# Motor_Driver.net
KiCad netlist of a schematic drawn in Altium Designer
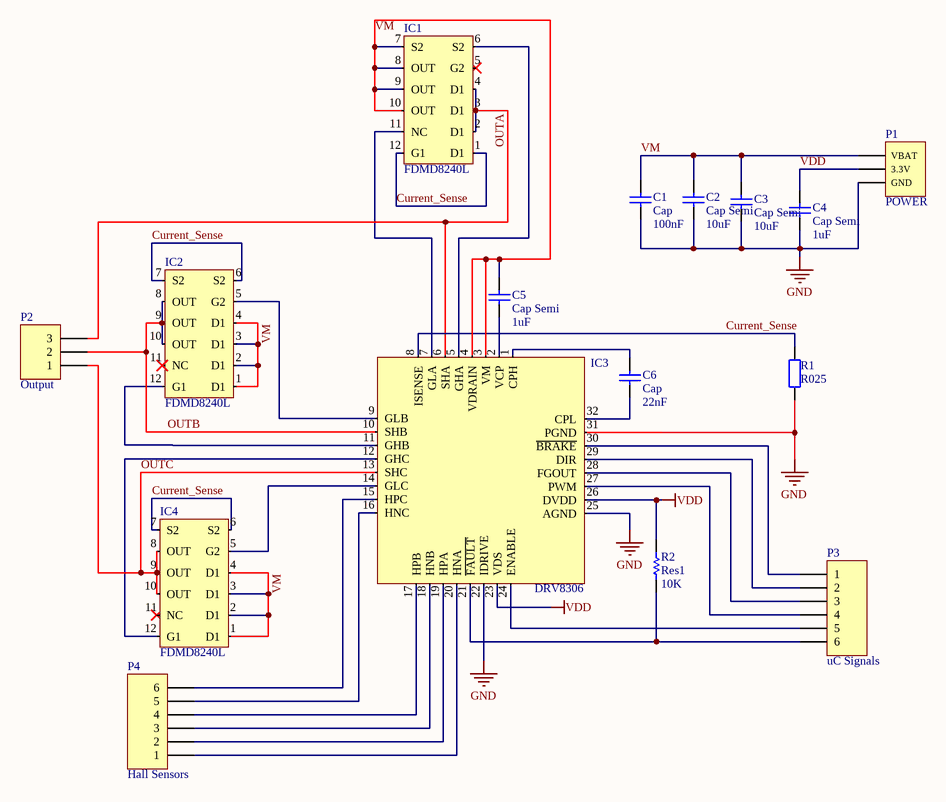
[diagram p0: Motor_Driver.SchDoc]

(export (version "E")
  (design (tool "Eeschema 10.0.6"))
  (components
    (comp (ref "C1")
      (value "Cap")
      (footprint "0402")
      (description "Multilayer Ceramic Capacitors MLCC - SMD/SMT 16volts 0.1uF 20% X7R")
      (fields (field (name "ALTIUM_VALUE") "100nF"))
      (libsource (lib "Miscellaneous Devices") (part "Cap"))
    )
    (comp (ref "C2")
      (value "Cap Semi")
      (footprint "CAP_TANT1206")
      (description "Tantalum Capacitors - Solid SMD 16V 10uF 1206 10% ESR=3Ohms")
      (fields (field (name "ALTIUM_VALUE") "10uF"))
      (libsource (lib "Miscellaneous Devices") (part "Cap Semi"))
    )
    (comp (ref "C3")
      (value "Cap Semi")
      (footprint "CAP_TANT1206")
      (description "Tantalum Capacitors - Solid SMD 16V 10uF 1206 10% ESR=3Ohms")
      (fields (field (name "ALTIUM_VALUE") "10uF"))
      (libsource (lib "Miscellaneous Devices") (part "Cap Semi"))
    )
    (comp (ref "C4")
      (value "Cap Semi")
      (footprint "0402")
      (description "Multilayer Ceramic Capacitors MLCC - SMD/SMT CGB 0402 16V 1uF JB 20%")
      (fields (field (name "ALTIUM_VALUE") "1uF"))
      (libsource (lib "Miscellaneous Devices") (part "Cap Semi"))
    )
    (comp (ref "C5")
      (value "Cap Semi")
      (footprint "0402")
      (description "Multilayer Ceramic Capacitors MLCC - SMD/SMT CGB 0402 16V 1uF JB 20%")
      (fields (field (name "ALTIUM_VALUE") "1uF"))
      (libsource (lib "Miscellaneous Devices") (part "Cap Semi"))
    )
    (comp (ref "C6")
      (value "Cap")
      (footprint "0402")
      (description "Capacitor")
      (fields (field (name "ALTIUM_VALUE") "22nF") (field (name "PUBLISHER") "Altium Limited"))
      (libsource (lib "Miscellaneous Devices") (part "Cap"))
    )
    (comp (ref "IC1")
      (value "FDMD8240L")
      (footprint "PQFN-12")
      (description "Dual N-Channel Power Trench MOSFET 40, 98A, 2.6mOhms")
      (libsource (lib "Motor_Driver") (part "FDMD8240L"))
    )
    (comp (ref "IC2")
      (value "FDMD8240L")
      (footprint "PQFN-12")
      (description "Dual N-Channel Power Trench MOSFET 40, 98A, 2.6mOhms")
      (libsource (lib "Motor_Driver") (part "FDMD8240L"))
    )
    (comp (ref "IC3")
      (value "DRV8306")
      (description "DRV8306 38-V Brushless DC Motor Controller")
      (libsource (lib "Motor_Driver") (part "DRV8306"))
    )
    (comp (ref "IC4")
      (value "FDMD8240L")
      (footprint "PQFN-12")
      (description "Dual N-Channel Power Trench MOSFET 40, 98A, 2.6mOhms")
      (libsource (lib "Motor_Driver") (part "FDMD8240L"))
    )
    (comp (ref "P1")
      (value "POWER")
      (footprint "HDR1X3")
      (description "Power Connector")
      (fields (field (name "PUBLISHER") "Altium Limited"))
      (libsource (lib "") (part "Header 3_1"))
    )
    (comp (ref "P2")
      (value "Output")
      (footprint "HDR1X3")
      (description "Motor Output")
      (fields (field (name "PUBLISHER") "Altium Limited"))
      (libsource (lib "Miscellaneous Connectors") (part "Header 3"))
    )
    (comp (ref "P3")
      (value "uC Signals")
      (footprint "HDR1X6")
      (description "Microcontroller connector")
      (fields (field (name "PUBLISHER") "Altium Limited"))
      (libsource (lib "Miscellaneous Connectors") (part "Header 6"))
    )
    (comp (ref "P4")
      (value "Hall Sensors")
      (footprint "HDR1X6")
      (description "Hall Sensors Connector")
      (fields (field (name "PUBLISHER") "Altium Limited"))
      (libsource (lib "") (part "Header 6_1"))
    )
    (comp (ref "R1")
      (value "R025")
      (footprint "RES2818")
      (description "Current Sense Resistors - SMD2818 10W .025ohms 1%")
      (libsource (lib "Motor_Driver") (part "WSHP2818"))
    )
    (comp (ref "R2")
      (value "Res1")
      (footprint "RES0402")
      (description "Thick Film Resistors - SMD 0.2watt 10Kohms 1% 100ppm")
      (fields (field (name "ALTIUM_VALUE") "10K"))
      (libsource (lib "Miscellaneous Devices") (part "Res1"))
    )
  )
  (nets
    (net (code "1") (name "/Current_Sense") (class "Default")
      (node (ref "IC1") (pin "1") (pinfunction "D1_1") (pintype "passive"))
      (node (ref "IC1") (pin "12") (pinfunction "G1_12") (pintype "passive"))
      (node (ref "IC2") (pin "6") (pinfunction "S2_6") (pintype "passive"))
      (node (ref "IC2") (pin "7") (pinfunction "S2_7") (pintype "passive"))
      (node (ref "IC3") (pin "8") (pinfunction "ISENSE_8") (pintype "input"))
      (node (ref "IC4") (pin "6") (pinfunction "S2_6") (pintype "passive"))
      (node (ref "IC4") (pin "7") (pinfunction "S2_7") (pintype "passive"))
      (node (ref "R1") (pin "2") (pinfunction "2_2") (pintype "passive"))
    )
    (net (code "2") (name "/OUTA") (class "Default")
      (node (ref "IC1") (pin "2") (pinfunction "D1_2") (pintype "passive"))
      (node (ref "IC1") (pin "3") (pinfunction "D1_3") (pintype "passive"))
      (node (ref "IC1") (pin "4") (pinfunction "D1_4") (pintype "passive"))
      (node (ref "IC3") (pin "6") (pinfunction "SHA_6") (pintype "input"))
      (node (ref "P2") (pin "3") (pinfunction "3_3") (pintype "passive"))
    )
    (net (code "3") (name "/OUTB") (class "Default")
      (node (ref "IC2") (pin "10") (pinfunction "OUT_10") (pintype "passive"))
      (node (ref "IC2") (pin "8") (pinfunction "OUT_8") (pintype "passive"))
      (node (ref "IC2") (pin "9") (pinfunction "OUT_9") (pintype "passive"))
      (node (ref "IC3") (pin "10") (pinfunction "SHB_10") (pintype "input"))
      (node (ref "P2") (pin "2") (pinfunction "2_2") (pintype "passive"))
    )
    (net (code "4") (name "/OUTC") (class "Default")
      (node (ref "IC3") (pin "13") (pinfunction "SHC_13") (pintype "input"))
      (node (ref "IC4") (pin "10") (pinfunction "OUT_10") (pintype "passive"))
      (node (ref "IC4") (pin "8") (pinfunction "OUT_8") (pintype "passive"))
      (node (ref "IC4") (pin "9") (pinfunction "OUT_9") (pintype "passive"))
      (node (ref "P2") (pin "1") (pinfunction "1_1") (pintype "passive"))
    )
    (net (code "5") (name "/VM") (class "Default")
      (node (ref "C1") (pin "2") (pinfunction "2_2") (pintype "passive"))
      (node (ref "C2") (pin "2") (pinfunction "2_2") (pintype "passive"))
      (node (ref "C3") (pin "2") (pinfunction "2_2") (pintype "passive"))
      (node (ref "C5") (pin "2") (pinfunction "2_2") (pintype "passive"))
      (node (ref "IC1") (pin "10") (pinfunction "OUT_10") (pintype "passive"))
      (node (ref "IC1") (pin "7") (pinfunction "S2_7") (pintype "passive"))
      (node (ref "IC1") (pin "8") (pinfunction "OUT_8") (pintype "passive"))
      (node (ref "IC1") (pin "9") (pinfunction "OUT_9") (pintype "passive"))
      (node (ref "IC2") (pin "1") (pinfunction "D1_1") (pintype "passive"))
      (node (ref "IC2") (pin "2") (pinfunction "D1_2") (pintype "passive"))
      (node (ref "IC2") (pin "3") (pinfunction "D1_3") (pintype "passive"))
      (node (ref "IC2") (pin "4") (pinfunction "D1_4") (pintype "passive"))
      (node (ref "IC3") (pin "3") (pinfunction "VM_3") (pintype "power_in"))
      (node (ref "IC3") (pin "4") (pinfunction "VDRAIN_4") (pintype "input"))
      (node (ref "IC4") (pin "1") (pinfunction "D1_1") (pintype "passive"))
      (node (ref "IC4") (pin "2") (pinfunction "D1_2") (pintype "passive"))
      (node (ref "IC4") (pin "3") (pinfunction "D1_3") (pintype "passive"))
      (node (ref "IC4") (pin "4") (pinfunction "D1_4") (pintype "passive"))
      (node (ref "P1") (pin "1") (pinfunction "VBAT_1") (pintype "passive"))
    )
    (net (code "6") (name "GND") (class "Default")
      (node (ref "C1") (pin "1") (pinfunction "1_1") (pintype "passive"))
      (node (ref "C2") (pin "1") (pinfunction "1_1") (pintype "passive"))
      (node (ref "C3") (pin "1") (pinfunction "1_1") (pintype "passive"))
      (node (ref "C4") (pin "1") (pinfunction "1_1") (pintype "passive"))
      (node (ref "IC3") (pin "22") (pinfunction "IDRIVE_22") (pintype "input"))
      (node (ref "IC3") (pin "25") (pinfunction "AGND_25") (pintype "power_in"))
      (node (ref "IC3") (pin "31") (pinfunction "PGND_31") (pintype "power_in"))
      (node (ref "P1") (pin "3") (pinfunction "GND_3") (pintype "passive"))
      (node (ref "R1") (pin "1") (pinfunction "1_1") (pintype "passive"))
    )
    (net (code "7") (name "Net-(IC1-NC)") (class "Default")
      (node (ref "IC1") (pin "11") (pinfunction "NC_11") (pintype "passive"))
      (node (ref "IC3") (pin "7") (pinfunction "GLA_7") (pintype "output"))
    )
    (net (code "8") (name "Net-(IC2-G1)") (class "Default")
      (node (ref "IC2") (pin "12") (pinfunction "G1_12") (pintype "passive"))
      (node (ref "IC3") (pin "11") (pinfunction "GHB_11") (pintype "output"))
    )
    (net (code "9") (name "Net-(IC2-G2)") (class "Default")
      (node (ref "IC2") (pin "5") (pinfunction "G2_5") (pintype "passive"))
      (node (ref "IC3") (pin "9") (pinfunction "GLB_9") (pintype "output"))
    )
    (net (code "10") (name "Net-(IC3-CPH)") (class "Default")
      (node (ref "C6") (pin "2") (pinfunction "2_2") (pintype "passive"))
      (node (ref "IC3") (pin "1") (pinfunction "CPH_1") (pintype "power_in"))
    )
    (net (code "11") (name "Net-(IC3-CPL)") (class "Default")
      (node (ref "C6") (pin "1") (pinfunction "1_1") (pintype "passive"))
      (node (ref "IC3") (pin "32") (pinfunction "CPL_32") (pintype "power_in"))
    )
    (net (code "12") (name "Net-(IC3-DIR)") (class "Default")
      (node (ref "IC3") (pin "29") (pinfunction "DIR_29") (pintype "input"))
      (node (ref "P3") (pin "2") (pinfunction "2_2") (pintype "passive"))
    )
    (net (code "13") (name "Net-(IC3-ENABLE)") (class "Default")
      (node (ref "IC3") (pin "24") (pinfunction "ENABLE_24") (pintype "input"))
      (node (ref "P3") (pin "5") (pinfunction "5_5") (pintype "passive"))
    )
    (net (code "14") (name "Net-(IC3-FGOUT)") (class "Default")
      (node (ref "IC3") (pin "28") (pinfunction "FGOUT_28") (pintype "open_collector"))
      (node (ref "P3") (pin "3") (pinfunction "3_3") (pintype "passive"))
    )
    (net (code "15") (name "Net-(IC3-GHA)") (class "Default")
      (node (ref "IC1") (pin "6") (pinfunction "S2_6") (pintype "passive"))
      (node (ref "IC3") (pin "5") (pinfunction "GHA_5") (pintype "output"))
    )
    (net (code "16") (name "Net-(IC3-GHC)") (class "Default")
      (node (ref "IC3") (pin "12") (pinfunction "GHC_12") (pintype "output"))
      (node (ref "IC4") (pin "12") (pinfunction "G1_12") (pintype "passive"))
    )
    (net (code "17") (name "Net-(IC3-GLC)") (class "Default")
      (node (ref "IC3") (pin "14") (pinfunction "GLC_14") (pintype "output"))
      (node (ref "IC4") (pin "5") (pinfunction "G2_5") (pintype "passive"))
    )
    (net (code "18") (name "Net-(IC3-HNA)") (class "Default")
      (node (ref "IC3") (pin "20") (pinfunction "HNA_20") (pintype "input"))
      (node (ref "P4") (pin "1") (pinfunction "1_1") (pintype "passive"))
    )
    (net (code "19") (name "Net-(IC3-HNB)") (class "Default")
      (node (ref "IC3") (pin "18") (pinfunction "HNB_18") (pintype "input"))
      (node (ref "P4") (pin "3") (pinfunction "3_3") (pintype "passive"))
    )
    (net (code "20") (name "Net-(IC3-HNC)") (class "Default")
      (node (ref "IC3") (pin "16") (pinfunction "HNC_16") (pintype "input"))
      (node (ref "P4") (pin "5") (pinfunction "5_5") (pintype "passive"))
    )
    (net (code "21") (name "Net-(IC3-HPA)") (class "Default")
      (node (ref "IC3") (pin "19") (pinfunction "HPA_19") (pintype "input"))
      (node (ref "P4") (pin "2") (pinfunction "2_2") (pintype "passive"))
    )
    (net (code "22") (name "Net-(IC3-HPB)") (class "Default")
      (node (ref "IC3") (pin "17") (pinfunction "HPB_17") (pintype "input"))
      (node (ref "P4") (pin "4") (pinfunction "4_4") (pintype "passive"))
    )
    (net (code "23") (name "Net-(IC3-HPC)") (class "Default")
      (node (ref "IC3") (pin "15") (pinfunction "HPC_15") (pintype "input"))
      (node (ref "P4") (pin "6") (pinfunction "6_6") (pintype "passive"))
    )
    (net (code "24") (name "Net-(IC3-PWM)") (class "Default")
      (node (ref "IC3") (pin "27") (pinfunction "PWM_27") (pintype "input"))
      (node (ref "P3") (pin "4") (pinfunction "4_4") (pintype "passive"))
    )
    (net (code "25") (name "Net-(IC3-VCP)") (class "Default")
      (node (ref "C5") (pin "1") (pinfunction "1_1") (pintype "passive"))
      (node (ref "IC3") (pin "2") (pinfunction "VCP_2") (pintype "power_in"))
    )
    (net (code "26") (name "Net-(IC3-~{BRAKE})") (class "Default")
      (node (ref "IC3") (pin "30") (pinfunction "~{BRAKE}_30") (pintype "input"))
      (node (ref "P3") (pin "1") (pinfunction "1_1") (pintype "passive"))
    )
    (net (code "27") (name "Net-(IC3-~{FAULT})") (class "Default")
      (node (ref "IC3") (pin "21") (pinfunction "~{FAULT}_21") (pintype "open_collector"))
      (node (ref "P3") (pin "6") (pinfunction "6_6") (pintype "passive"))
      (node (ref "R2") (pin "1") (pinfunction "1_1") (pintype "passive"))
    )
    (net (code "28") (name "VDD") (class "Default")
      (node (ref "C4") (pin "2") (pinfunction "2_2") (pintype "passive"))
      (node (ref "IC3") (pin "23") (pinfunction "VDS_23") (pintype "input"))
      (node (ref "IC3") (pin "26") (pinfunction "DVDD_26") (pintype "power_in"))
      (node (ref "P1") (pin "2") (pinfunction "3.3V_2") (pintype "passive"))
      (node (ref "R2") (pin "2") (pinfunction "2_2") (pintype "passive"))
    )
    (net (code "29") (name "unconnected-(IC1-G2-Pad5)") (class "Default")
      (node (ref "IC1") (pin "5") (pinfunction "G2_5") (pintype "passive+no_connect"))
    )
    (net (code "30") (name "unconnected-(IC2-NC-Pad11)") (class "Default")
      (node (ref "IC2") (pin "11") (pinfunction "NC_11") (pintype "passive+no_connect"))
    )
    (net (code "31") (name "unconnected-(IC4-NC-Pad11)") (class "Default")
      (node (ref "IC4") (pin "11") (pinfunction "NC_11") (pintype "passive+no_connect"))
    )
  )
)
